# Avery_Bellis_board.net
KiCad netlist of a schematic drawn in EAGLE
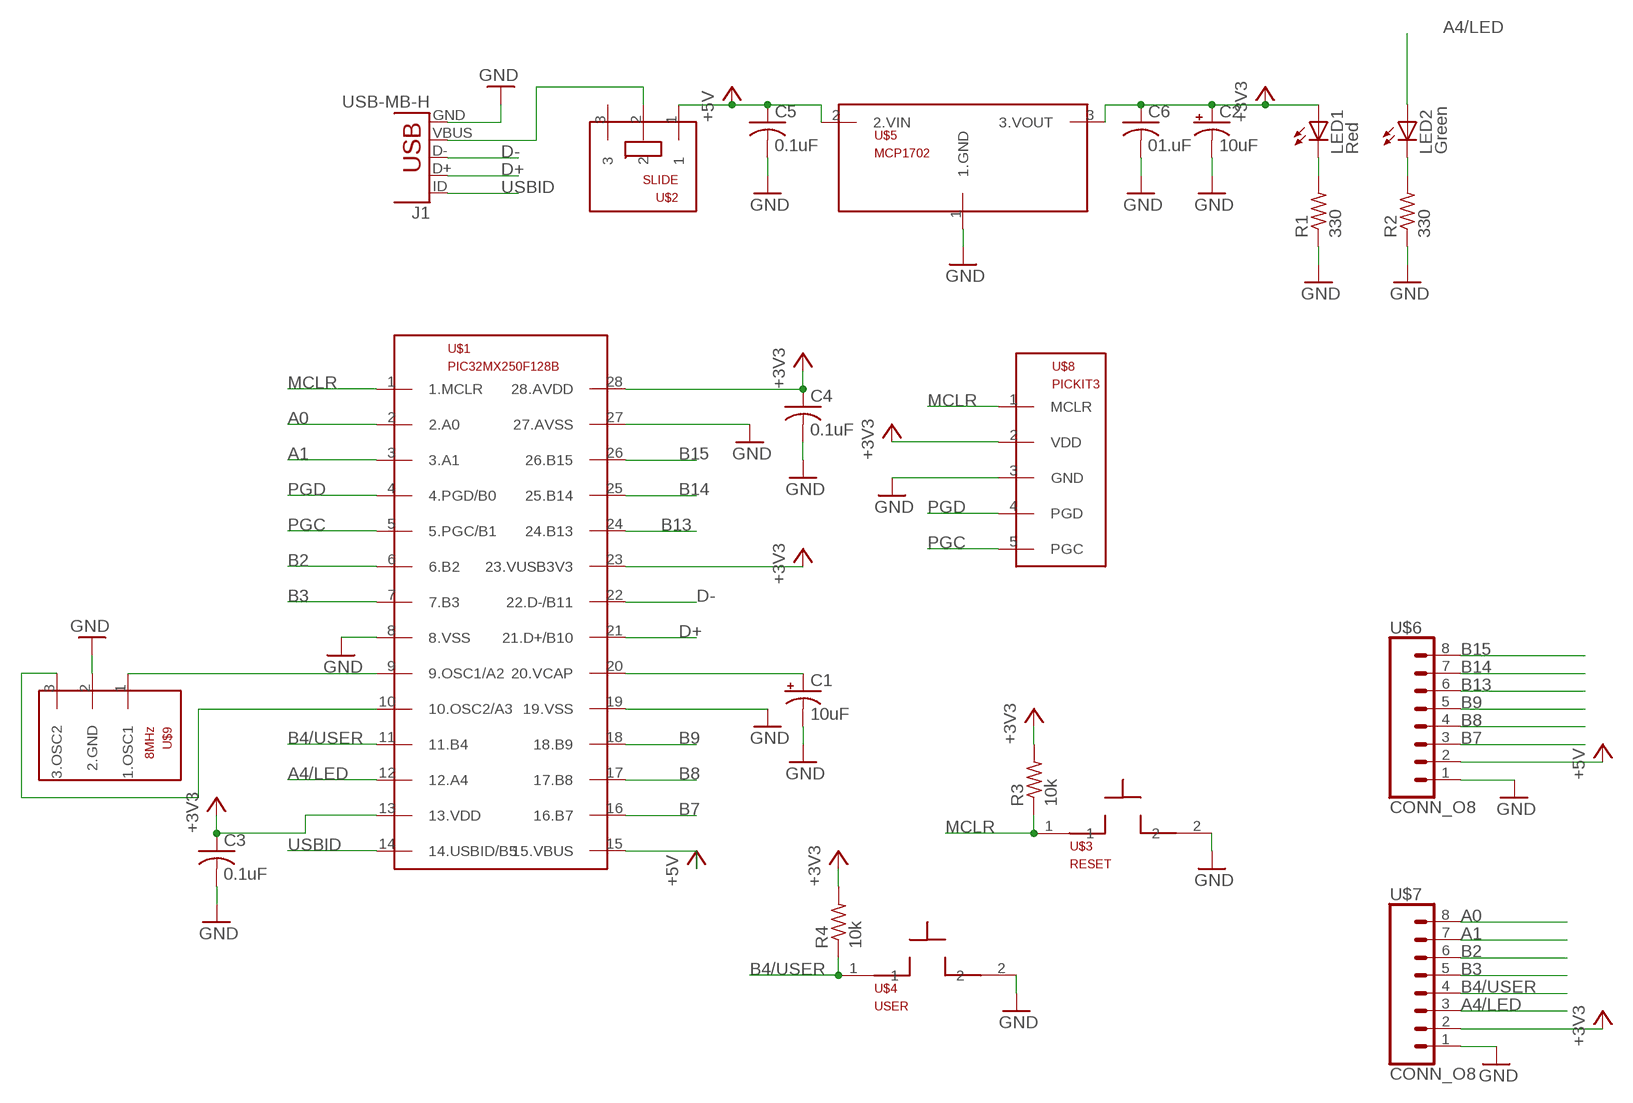
[diagram p0: schematic, sheet 1]

(export (version "E")
  (design (tool "Eeschema 10.0.6"))
  (components
    (comp (ref "C1")
      (value "10uF")
      (footprint "eagle-import:B45181B")
      (libsource (lib "eagle-import") (part "CPOL-USB45181B"))
    )
    (comp (ref "C2")
      (value "10uF")
      (footprint "eagle-import:B45181B")
      (libsource (lib "eagle-import") (part "CPOL-USB45181B"))
    )
    (comp (ref "C3")
      (value "0.1uF")
      (footprint "eagle-import:C025-025X050")
      (libsource (lib "eagle-import") (part "C-US025-025X050"))
    )
    (comp (ref "C4")
      (value "0.1uF")
      (footprint "eagle-import:C025-025X050")
      (libsource (lib "eagle-import") (part "C-US025-025X050"))
    )
    (comp (ref "C5")
      (value "0.1uF")
      (footprint "eagle-import:C025-025X050")
      (libsource (lib "eagle-import") (part "C-US025-025X050"))
    )
    (comp (ref "C6")
      (value "01.uF")
      (footprint "eagle-import:C025-025X050")
      (libsource (lib "eagle-import") (part "C-US025-025X050"))
    )
    (comp (ref "J1")
      (value "USB-MB-H")
      (footprint "eagle-import:USB-MB-H")
      (libsource (lib "eagle-import") (part "USB-MB-H"))
    )
    (comp (ref "LED1")
      (value "Red")
      (footprint "eagle-import:LED3MM")
      (libsource (lib "eagle-import") (part "LED3MM"))
    )
    (comp (ref "LED2")
      (value "Green")
      (footprint "eagle-import:LED3MM")
      (libsource (lib "eagle-import") (part "LED3MM"))
    )
    (comp (ref "R1")
      (value "330")
      (footprint "eagle-import:0207_10")
      (libsource (lib "eagle-import") (part "R-US_0207/10"))
    )
    (comp (ref "R2")
      (value "330")
      (footprint "eagle-import:0207_10")
      (libsource (lib "eagle-import") (part "R-US_0207/10"))
    )
    (comp (ref "R3")
      (value "10k")
      (footprint "eagle-import:0207_10")
      (libsource (lib "eagle-import") (part "R-US_0207/10"))
    )
    (comp (ref "R4")
      (value "10k")
      (footprint "eagle-import:0207_10")
      (libsource (lib "eagle-import") (part "R-US_0207/10"))
    )
    (comp (ref "U$1")
      (value "PIC32MX250F128B")
      (footprint "eagle-import:DIL28-3")
      (libsource (lib "eagle-import") (part "PIC32MX250F128B"))
    )
    (comp (ref "U$2")
      (value "SLIDE")
      (footprint "eagle-import:SLIDE")
      (libsource (lib "eagle-import") (part "SLIDE"))
    )
    (comp (ref "U$3")
      (value "RESET")
      (footprint "eagle-import:PUSHB")
      (libsource (lib "eagle-import") (part "PUSHB"))
    )
    (comp (ref "U$4")
      (value "USER")
      (footprint "eagle-import:PUSHB")
      (libsource (lib "eagle-import") (part "PUSHB"))
    )
    (comp (ref "U$5")
      (value "MCP1702")
      (footprint "eagle-import:TO92")
      (libsource (lib "eagle-import") (part "MCP1702"))
    )
    (comp (ref "U$6")
      (value "CONN_O8")
      (footprint "eagle-import:1X08")
      (libsource (lib "eagle-import") (part "CONN_O8"))
    )
    (comp (ref "U$7")
      (value "CONN_O8")
      (footprint "eagle-import:1X08")
      (libsource (lib "eagle-import") (part "CONN_O8"))
    )
    (comp (ref "U$8")
      (value "PICKIT3")
      (footprint "eagle-import:1X05")
      (libsource (lib "eagle-import") (part "PICKIT3"))
    )
    (comp (ref "U$9")
      (value "8MHz")
      (footprint "eagle-import:OSC")
      (libsource (lib "eagle-import") (part "OSC"))
    )
  )
  (nets
    (net (code "1") (name "+3V3") (class "Default")
      (node (ref "C2") (pin "+") (pinfunction "+_+") (pintype "passive"))
      (node (ref "C3") (pin "1") (pinfunction "1_1") (pintype "passive"))
      (node (ref "C4") (pin "1") (pinfunction "1_1") (pintype "passive"))
      (node (ref "C6") (pin "1") (pinfunction "1_1") (pintype "passive"))
      (node (ref "LED1") (pin "A") (pinfunction "A_A") (pintype "passive"))
      (node (ref "R3") (pin "2") (pinfunction "2_2") (pintype "passive"))
      (node (ref "R4") (pin "2") (pinfunction "2_2") (pintype "passive"))
      (node (ref "U$1") (pin "13") (pinfunction "13.VDD_13") (pintype "bidirectional"))
      (node (ref "U$1") (pin "23") (pinfunction "23.VUSB3V3_23") (pintype "bidirectional"))
      (node (ref "U$1") (pin "28") (pinfunction "28.AVDD_28") (pintype "bidirectional"))
      (node (ref "U$5") (pin "3") (pinfunction "3.VOUT_3") (pintype "bidirectional"))
      (node (ref "U$7") (pin "2") (pinfunction "2_2") (pintype "passive"))
      (node (ref "U$8") (pin "2") (pinfunction "VDD_2") (pintype "bidirectional"))
    )
    (net (code "2") (name "+5V") (class "Default")
      (node (ref "C5") (pin "1") (pinfunction "1_1") (pintype "passive"))
      (node (ref "U$1") (pin "15") (pinfunction "15.VBUS_15") (pintype "bidirectional"))
      (node (ref "U$2") (pin "1") (pinfunction "1_1") (pintype "bidirectional"))
      (node (ref "U$5") (pin "2") (pinfunction "2.VIN_2") (pintype "bidirectional"))
      (node (ref "U$6") (pin "2") (pinfunction "2_2") (pintype "passive"))
    )
    (net (code "3") (name "/A0") (class "Default")
      (node (ref "U$1") (pin "2") (pinfunction "2.A0_2") (pintype "bidirectional"))
      (node (ref "U$7") (pin "8") (pinfunction "8_8") (pintype "passive"))
    )
    (net (code "4") (name "/A1") (class "Default")
      (node (ref "U$1") (pin "3") (pinfunction "3.A1_3") (pintype "bidirectional"))
      (node (ref "U$7") (pin "7") (pinfunction "7_7") (pintype "passive"))
    )
    (net (code "5") (name "/A4{slash}LED") (class "Default")
      (node (ref "LED2") (pin "A") (pinfunction "A_A") (pintype "passive"))
      (node (ref "U$1") (pin "12") (pinfunction "12.A4_12") (pintype "bidirectional"))
      (node (ref "U$7") (pin "3") (pinfunction "3_3") (pintype "passive"))
    )
    (net (code "6") (name "/B2") (class "Default")
      (node (ref "U$1") (pin "6") (pinfunction "6.B2_6") (pintype "bidirectional"))
      (node (ref "U$7") (pin "6") (pinfunction "6_6") (pintype "passive"))
    )
    (net (code "7") (name "/B3") (class "Default")
      (node (ref "U$1") (pin "7") (pinfunction "7.B3_7") (pintype "bidirectional"))
      (node (ref "U$7") (pin "5") (pinfunction "5_5") (pintype "passive"))
    )
    (net (code "8") (name "/B4{slash}USER") (class "Default")
      (node (ref "R4") (pin "1") (pinfunction "1_1") (pintype "passive"))
      (node (ref "U$1") (pin "11") (pinfunction "11.B4_11") (pintype "bidirectional"))
      (node (ref "U$4") (pin "1") (pinfunction "1_1") (pintype "bidirectional"))
      (node (ref "U$7") (pin "4") (pinfunction "4_4") (pintype "passive"))
    )
    (net (code "9") (name "/B7") (class "Default")
      (node (ref "U$1") (pin "16") (pinfunction "16.B7_16") (pintype "bidirectional"))
      (node (ref "U$6") (pin "3") (pinfunction "3_3") (pintype "passive"))
    )
    (net (code "10") (name "/B8") (class "Default")
      (node (ref "U$1") (pin "17") (pinfunction "17.B8_17") (pintype "bidirectional"))
      (node (ref "U$6") (pin "4") (pinfunction "4_4") (pintype "passive"))
    )
    (net (code "11") (name "/B9") (class "Default")
      (node (ref "U$1") (pin "18") (pinfunction "18.B9_18") (pintype "bidirectional"))
      (node (ref "U$6") (pin "5") (pinfunction "5_5") (pintype "passive"))
    )
    (net (code "12") (name "/B13") (class "Default")
      (node (ref "U$1") (pin "24") (pinfunction "24.B13_24") (pintype "bidirectional"))
      (node (ref "U$6") (pin "6") (pinfunction "6_6") (pintype "passive"))
    )
    (net (code "13") (name "/B14") (class "Default")
      (node (ref "U$1") (pin "25") (pinfunction "25.B14_25") (pintype "bidirectional"))
      (node (ref "U$6") (pin "7") (pinfunction "7_7") (pintype "passive"))
    )
    (net (code "14") (name "/B15") (class "Default")
      (node (ref "U$1") (pin "26") (pinfunction "26.B15_26") (pintype "bidirectional"))
      (node (ref "U$6") (pin "8") (pinfunction "8_8") (pintype "passive"))
    )
    (net (code "15") (name "/D+") (class "Default")
      (node (ref "J1") (pin "D+") (pinfunction "D+_D+") (pintype "bidirectional"))
      (node (ref "U$1") (pin "21") (pinfunction "21.D+/B10_21") (pintype "bidirectional"))
    )
    (net (code "16") (name "/D-") (class "Default")
      (node (ref "J1") (pin "D-") (pinfunction "D-_D-") (pintype "bidirectional"))
      (node (ref "U$1") (pin "22") (pinfunction "22.D-/B11_22") (pintype "bidirectional"))
    )
    (net (code "17") (name "/MCLR") (class "Default")
      (node (ref "R3") (pin "1") (pinfunction "1_1") (pintype "passive"))
      (node (ref "U$1") (pin "1") (pinfunction "1.MCLR_1") (pintype "bidirectional"))
      (node (ref "U$3") (pin "1") (pinfunction "1_1") (pintype "bidirectional"))
      (node (ref "U$8") (pin "1") (pinfunction "MCLR_1") (pintype "bidirectional"))
    )
    (net (code "18") (name "/PGC") (class "Default")
      (node (ref "U$1") (pin "5") (pinfunction "5.PGC/B1_5") (pintype "bidirectional"))
      (node (ref "U$8") (pin "5") (pinfunction "PGC_5") (pintype "bidirectional"))
    )
    (net (code "19") (name "/PGD") (class "Default")
      (node (ref "U$1") (pin "4") (pinfunction "4.PGD/B0_4") (pintype "bidirectional"))
      (node (ref "U$8") (pin "4") (pinfunction "PGD_4") (pintype "bidirectional"))
    )
    (net (code "20") (name "/USBID") (class "Default")
      (node (ref "J1") (pin "ID") (pinfunction "ID_ID") (pintype "bidirectional"))
      (node (ref "U$1") (pin "14") (pinfunction "14.USBID/B5_14") (pintype "bidirectional"))
    )
    (net (code "21") (name "GND") (class "Default")
      (node (ref "C1") (pin "-") (pinfunction "-_-") (pintype "passive"))
      (node (ref "C2") (pin "-") (pinfunction "-_-") (pintype "passive"))
      (node (ref "C3") (pin "2") (pinfunction "2_2") (pintype "passive"))
      (node (ref "C4") (pin "2") (pinfunction "2_2") (pintype "passive"))
      (node (ref "C5") (pin "2") (pinfunction "2_2") (pintype "passive"))
      (node (ref "C6") (pin "2") (pinfunction "2_2") (pintype "passive"))
      (node (ref "J1") (pin "GND") (pinfunction "GND_GND") (pintype "bidirectional"))
      (node (ref "R1") (pin "1") (pinfunction "1_1") (pintype "passive"))
      (node (ref "R2") (pin "1") (pinfunction "1_1") (pintype "passive"))
      (node (ref "U$1") (pin "19") (pinfunction "19.VSS_19") (pintype "bidirectional"))
      (node (ref "U$1") (pin "27") (pinfunction "27.AVSS_27") (pintype "bidirectional"))
      (node (ref "U$1") (pin "8") (pinfunction "8.VSS_8") (pintype "bidirectional"))
      (node (ref "U$3") (pin "2") (pinfunction "2_2") (pintype "bidirectional"))
      (node (ref "U$4") (pin "2") (pinfunction "2_2") (pintype "bidirectional"))
      (node (ref "U$5") (pin "1") (pinfunction "1.GND_1") (pintype "bidirectional"))
      (node (ref "U$6") (pin "1") (pinfunction "1_1") (pintype "passive"))
      (node (ref "U$7") (pin "1") (pinfunction "1_1") (pintype "passive"))
      (node (ref "U$8") (pin "3") (pinfunction "GND_3") (pintype "bidirectional"))
      (node (ref "U$9") (pin "2") (pinfunction "2.GND_2") (pintype "bidirectional"))
    )
    (net (code "22") (name "Net-(J1-PadVBUS)") (class "Default")
      (node (ref "J1") (pin "VBUS") (pinfunction "VBUS_VBUS") (pintype "bidirectional"))
      (node (ref "U$2") (pin "2") (pinfunction "2_2") (pintype "bidirectional"))
    )
    (net (code "23") (name "Net-(LED1-C)") (class "Default")
      (node (ref "LED1") (pin "K") (pinfunction "C_K") (pintype "passive"))
      (node (ref "R1") (pin "2") (pinfunction "2_2") (pintype "passive"))
    )
    (net (code "24") (name "Net-(LED2-C)") (class "Default")
      (node (ref "LED2") (pin "K") (pinfunction "C_K") (pintype "passive"))
      (node (ref "R2") (pin "2") (pinfunction "2_2") (pintype "passive"))
    )
    (net (code "25") (name "Net-(U$1-9.OSC1{slash}A2)") (class "Default")
      (node (ref "U$1") (pin "9") (pinfunction "9.OSC1/A2_9") (pintype "bidirectional"))
      (node (ref "U$9") (pin "1") (pinfunction "1.OSC1_1") (pintype "bidirectional"))
    )
    (net (code "26") (name "Net-(U$1-10.OSC2{slash}A3)") (class "Default")
      (node (ref "U$1") (pin "10") (pinfunction "10.OSC2/A3_10") (pintype "bidirectional"))
      (node (ref "U$9") (pin "3") (pinfunction "3.OSC2_3") (pintype "bidirectional"))
    )
    (net (code "27") (name "Net-(U$1-20.VCAP)") (class "Default")
      (node (ref "C1") (pin "+") (pinfunction "+_+") (pintype "passive"))
      (node (ref "U$1") (pin "20") (pinfunction "20.VCAP_20") (pintype "bidirectional"))
    )
    (net (code "28") (name "unconnected-(U$2-Pad3)") (class "Default")
      (node (ref "U$2") (pin "3") (pinfunction "3_3") (pintype "bidirectional"))
    )
  )
)
